# Easy-EDA-project.net
KiCad netlist of a schematic drawn in EasyEDA
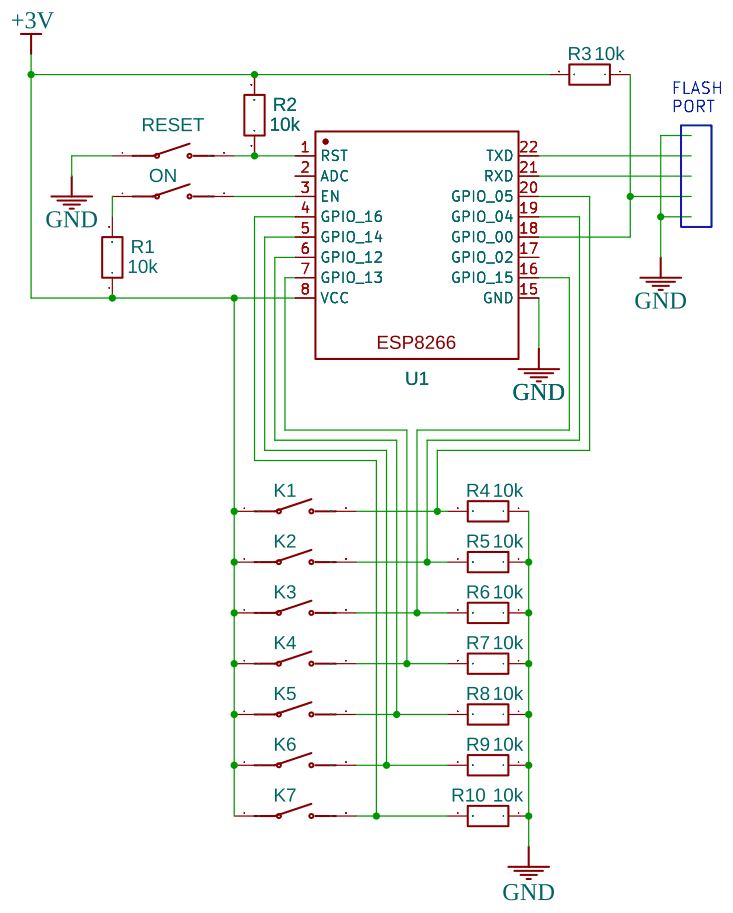
[diagram p0: schematic sheet]

(export (version "E")
  (design (tool "Eeschema 10.0.6"))
  (components
    (comp (ref "K1")
      (value "SWITCH,3*6*5PLASTIC HEAD WHITE,260G, 0.25MM,SMD")
      (fields
        (field (name "BOM_Manufacturer Part") "Switch,3*6*5Plastic head white,260G, 0.25mm,SMD")
        (field (name "BOM_Supplier Part") "C71855")
      )
      (libsource (lib "") (part "SWITCH,3*6*5PLASTIC HEAD WHITE,260G, 0.25MM,SMD"))
    )
    (comp (ref "K2")
      (value "SWITCH,3*6*5PLASTIC HEAD WHITE,260G, 0.25MM,SMD")
      (fields
        (field (name "BOM_Manufacturer Part") "Switch,3*6*5Plastic head white,260G, 0.25mm,SMD")
        (field (name "BOM_Supplier Part") "C71855")
      )
      (libsource (lib "") (part "SWITCH,3*6*5PLASTIC HEAD WHITE,260G, 0.25MM,SMD"))
    )
    (comp (ref "K3")
      (value "SWITCH,3*6*5PLASTIC HEAD WHITE,260G, 0.25MM,SMD")
      (fields
        (field (name "BOM_Manufacturer Part") "Switch,3*6*5Plastic head white,260G, 0.25mm,SMD")
        (field (name "BOM_Supplier Part") "C71855")
      )
      (libsource (lib "") (part "SWITCH,3*6*5PLASTIC HEAD WHITE,260G, 0.25MM,SMD"))
    )
    (comp (ref "K4")
      (value "SWITCH,3*6*5PLASTIC HEAD WHITE,260G, 0.25MM,SMD")
      (fields
        (field (name "BOM_Manufacturer Part") "Switch,3*6*5Plastic head white,260G, 0.25mm,SMD")
        (field (name "BOM_Supplier Part") "C71855")
      )
      (libsource (lib "") (part "SWITCH,3*6*5PLASTIC HEAD WHITE,260G, 0.25MM,SMD"))
    )
    (comp (ref "K5")
      (value "SWITCH,3*6*5PLASTIC HEAD WHITE,260G, 0.25MM,SMD")
      (fields
        (field (name "BOM_Manufacturer Part") "Switch,3*6*5Plastic head white,260G, 0.25mm,SMD")
        (field (name "BOM_Supplier Part") "C71855")
      )
      (libsource (lib "") (part "SWITCH,3*6*5PLASTIC HEAD WHITE,260G, 0.25MM,SMD"))
    )
    (comp (ref "K6")
      (value "SWITCH,3*6*5PLASTIC HEAD WHITE,260G, 0.25MM,SMD")
      (fields
        (field (name "BOM_Manufacturer Part") "Switch,3*6*5Plastic head white,260G, 0.25mm,SMD")
        (field (name "BOM_Supplier Part") "C71855")
      )
      (libsource (lib "") (part "SWITCH,3*6*5PLASTIC HEAD WHITE,260G, 0.25MM,SMD"))
    )
    (comp (ref "K7")
      (value "SWITCH,3*6*5PLASTIC HEAD WHITE,260G, 0.25MM,SMD")
      (fields
        (field (name "BOM_Manufacturer Part") "Switch,3*6*5Plastic head white,260G, 0.25mm,SMD")
        (field (name "BOM_Supplier Part") "C71855")
      )
      (libsource (lib "") (part "SWITCH,3*6*5PLASTIC HEAD WHITE,260G, 0.25MM,SMD"))
    )
    (comp (ref "ON")
      (value "SWITCH,3*6*5PLASTIC HEAD WHITE,260G, 0.25MM,SMD")
      (fields
        (field (name "BOM_Manufacturer Part") "Switch,3*6*5Plastic head white,260G, 0.25mm,SMD")
        (field (name "BOM_Supplier Part") "C71855")
      )
      (libsource (lib "") (part "SWITCH,3*6*5PLASTIC HEAD WHITE,260G, 0.25MM,SMD_1"))
    )
    (comp (ref "R1")
      (value "10k")
      (fields (field (name "BOM_Manufacturer Part") "?"))
      (libsource (lib "") (part "Res_AXIAL-0.3(1/8W)_EU_1"))
    )
    (comp (ref "R2")
      (value "10k")
      (fields (field (name "BOM_Manufacturer Part") "?"))
      (libsource (lib "") (part "Res_AXIAL-0.3(1/8W)_EU_1"))
    )
    (comp (ref "R3")
      (value "10k")
      (fields (field (name "BOM_Manufacturer Part") "?"))
      (libsource (lib "") (part "Res_AXIAL-0.3(1/8W)_EU"))
    )
    (comp (ref "R4")
      (value "10k")
      (fields (field (name "BOM_Manufacturer Part") "?"))
      (libsource (lib "") (part "Res_AXIAL-0.3(1/8W)_EU"))
    )
    (comp (ref "R5")
      (value "10k")
      (fields (field (name "BOM_Manufacturer Part") "?"))
      (libsource (lib "") (part "Res_AXIAL-0.3(1/8W)_EU"))
    )
    (comp (ref "R6")
      (value "10k")
      (fields (field (name "BOM_Manufacturer Part") "?"))
      (libsource (lib "") (part "Res_AXIAL-0.3(1/8W)_EU"))
    )
    (comp (ref "R7")
      (value "10k")
      (fields (field (name "BOM_Manufacturer Part") "?"))
      (libsource (lib "") (part "Res_AXIAL-0.3(1/8W)_EU"))
    )
    (comp (ref "R8")
      (value "10k")
      (fields (field (name "BOM_Manufacturer Part") "?"))
      (libsource (lib "") (part "Res_AXIAL-0.3(1/8W)_EU"))
    )
    (comp (ref "R9")
      (value "10k")
      (fields (field (name "BOM_Manufacturer Part") "?"))
      (libsource (lib "") (part "Res_AXIAL-0.3(1/8W)_EU"))
    )
    (comp (ref "R10")
      (value "10k")
      (fields (field (name "BOM_Manufacturer Part") "?"))
      (libsource (lib "") (part "Res_AXIAL-0.3(1/8W)_EU"))
    )
    (comp (ref "RESET")
      (value "SWITCH,3*6*5PLASTIC HEAD WHITE,260G, 0.25MM,SMD")
      (fields
        (field (name "BOM_Manufacturer Part") "Switch,3*6*5Plastic head white,260G, 0.25mm,SMD")
        (field (name "BOM_Supplier Part") "C71855")
      )
      (libsource (lib "") (part "SWITCH,3*6*5PLASTIC HEAD WHITE,260G, 0.25MM,SMD_2"))
    )
    (comp (ref "U1")
      (value "esp8266-12")
      (fields (field (name "BOM_Manufacturer Part") "New SchematicLib"))
      (libsource (lib "") (part "Unknown_530_285"))
    )
  )
  (nets
    (net (code "1") (name "+3V") (class "Default")
      (node (ref "K1") (pin "1") (pinfunction "1_1") (pintype "unspecified"))
      (node (ref "K2") (pin "1") (pinfunction "1_1") (pintype "unspecified"))
      (node (ref "K3") (pin "1") (pinfunction "1_1") (pintype "unspecified"))
      (node (ref "K4") (pin "1") (pinfunction "1_1") (pintype "unspecified"))
      (node (ref "K5") (pin "1") (pinfunction "1_1") (pintype "unspecified"))
      (node (ref "K6") (pin "1") (pinfunction "1_1") (pintype "unspecified"))
      (node (ref "K7") (pin "1") (pinfunction "1_1") (pintype "unspecified"))
      (node (ref "R1") (pin "1") (pinfunction "1_1") (pintype "unspecified"))
      (node (ref "R2") (pin "2") (pinfunction "2_2") (pintype "unspecified"))
      (node (ref "R3") (pin "2") (pinfunction "2_2") (pintype "unspecified"))
      (node (ref "U1") (pin "8") (pinfunction "VCC_8") (pintype "unspecified"))
    )
    (net (code "2") (name "GND") (class "Default")
      (node (ref "R10") (pin "1") (pinfunction "1_1") (pintype "unspecified"))
      (node (ref "R4") (pin "1") (pinfunction "1_1") (pintype "unspecified"))
      (node (ref "R5") (pin "1") (pinfunction "1_1") (pintype "unspecified"))
      (node (ref "R6") (pin "1") (pinfunction "1_1") (pintype "unspecified"))
      (node (ref "R7") (pin "1") (pinfunction "1_1") (pintype "unspecified"))
      (node (ref "R8") (pin "1") (pinfunction "1_1") (pintype "unspecified"))
      (node (ref "R9") (pin "1") (pinfunction "1_1") (pintype "unspecified"))
      (node (ref "RESET") (pin "1") (pinfunction "1_1") (pintype "unspecified"))
      (node (ref "U1") (pin "15") (pinfunction "GND_15") (pintype "unspecified"))
    )
    (net (code "3") (name "Net-(ON-Pad1)") (class "Default")
      (node (ref "ON") (pin "1") (pinfunction "1_1") (pintype "unspecified"))
      (node (ref "R1") (pin "2") (pinfunction "2_2") (pintype "unspecified"))
    )
    (net (code "4") (name "Net-(U1-EN)") (class "Default")
      (node (ref "ON") (pin "2") (pinfunction "2_2") (pintype "unspecified"))
      (node (ref "U1") (pin "3") (pinfunction "EN_3") (pintype "unspecified"))
    )
    (net (code "5") (name "Net-(U1-GPIO_00)") (class "Default")
      (node (ref "R3") (pin "1") (pinfunction "1_1") (pintype "unspecified"))
      (node (ref "U1") (pin "18") (pinfunction "GPIO_00_18") (pintype "unspecified"))
    )
    (net (code "6") (name "Net-(U1-GPIO_04)") (class "Default")
      (node (ref "K2") (pin "2") (pinfunction "2_2") (pintype "unspecified"))
      (node (ref "R5") (pin "2") (pinfunction "2_2") (pintype "unspecified"))
      (node (ref "U1") (pin "19") (pinfunction "GPIO_04_19") (pintype "unspecified"))
    )
    (net (code "7") (name "Net-(U1-GPIO_05)") (class "Default")
      (node (ref "K1") (pin "2") (pinfunction "2_2") (pintype "unspecified"))
      (node (ref "R4") (pin "2") (pinfunction "2_2") (pintype "unspecified"))
      (node (ref "U1") (pin "20") (pinfunction "GPIO_05_20") (pintype "unspecified"))
    )
    (net (code "8") (name "Net-(U1-GPIO_12)") (class "Default")
      (node (ref "K5") (pin "2") (pinfunction "2_2") (pintype "unspecified"))
      (node (ref "R8") (pin "2") (pinfunction "2_2") (pintype "unspecified"))
      (node (ref "U1") (pin "6") (pinfunction "GPIO_12_6") (pintype "unspecified"))
    )
    (net (code "9") (name "Net-(U1-GPIO_13)") (class "Default")
      (node (ref "K4") (pin "2") (pinfunction "2_2") (pintype "unspecified"))
      (node (ref "R7") (pin "2") (pinfunction "2_2") (pintype "unspecified"))
      (node (ref "U1") (pin "7") (pinfunction "GPIO_13_7") (pintype "unspecified"))
    )
    (net (code "10") (name "Net-(U1-GPIO_14)") (class "Default")
      (node (ref "K6") (pin "2") (pinfunction "2_2") (pintype "unspecified"))
      (node (ref "R9") (pin "2") (pinfunction "2_2") (pintype "unspecified"))
      (node (ref "U1") (pin "5") (pinfunction "GPIO_14_5") (pintype "unspecified"))
    )
    (net (code "11") (name "Net-(U1-GPIO_15)") (class "Default")
      (node (ref "K3") (pin "2") (pinfunction "2_2") (pintype "unspecified"))
      (node (ref "R6") (pin "2") (pinfunction "2_2") (pintype "unspecified"))
      (node (ref "U1") (pin "16") (pinfunction "GPIO_15_16") (pintype "unspecified"))
    )
    (net (code "12") (name "Net-(U1-GPIO_16)") (class "Default")
      (node (ref "K7") (pin "2") (pinfunction "2_2") (pintype "unspecified"))
      (node (ref "R10") (pin "2") (pinfunction "2_2") (pintype "unspecified"))
      (node (ref "U1") (pin "4") (pinfunction "GPIO_16_4") (pintype "unspecified"))
    )
    (net (code "13") (name "Net-(U1-RST)") (class "Default")
      (node (ref "R2") (pin "1") (pinfunction "1_1") (pintype "unspecified"))
      (node (ref "RESET") (pin "2") (pinfunction "2_2") (pintype "unspecified"))
      (node (ref "U1") (pin "1") (pinfunction "RST_1") (pintype "unspecified"))
    )
    (net (code "14") (name "unconnected-(U1-ADC-Pad2)") (class "Default")
      (node (ref "U1") (pin "2") (pinfunction "ADC_2") (pintype "unspecified"))
    )
    (net (code "15") (name "unconnected-(U1-GPIO_02-Pad17)") (class "Default")
      (node (ref "U1") (pin "17") (pinfunction "GPIO_02_17") (pintype "unspecified"))
    )
    (net (code "16") (name "unconnected-(U1-RXD-Pad21)") (class "Default")
      (node (ref "U1") (pin "21") (pinfunction "RXD_21") (pintype "unspecified"))
    )
    (net (code "17") (name "unconnected-(U1-TXD-Pad22)") (class "Default")
      (node (ref "U1") (pin "22") (pinfunction "TXD_22") (pintype "unspecified"))
    )
  )
)
